# Adapterplatine.net
KiCad netlist of a schematic drawn in EAGLE
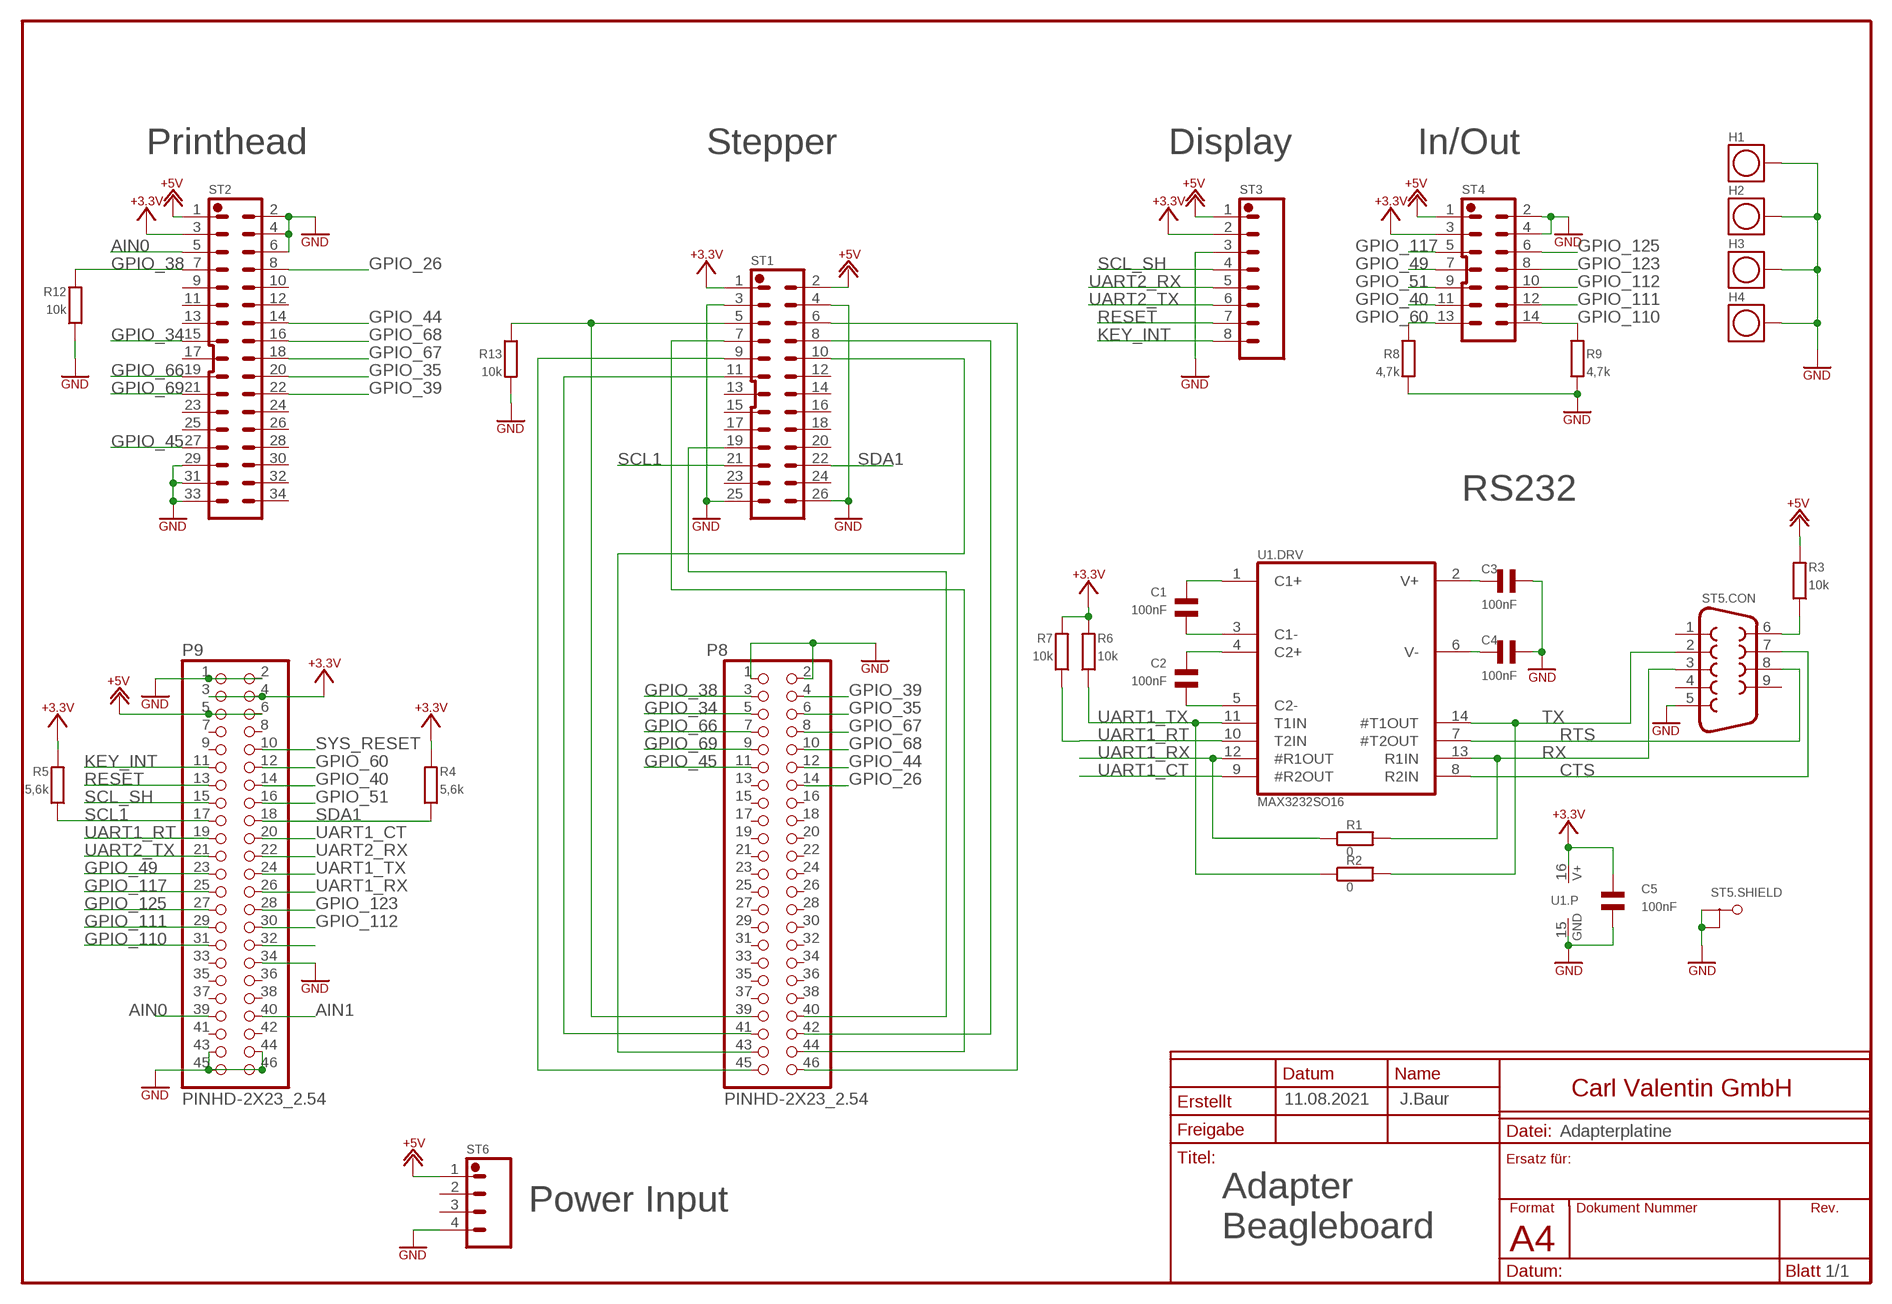
[diagram p0: schematic, sheet 1]

(export (version "E")
  (design (tool "Eeschema 10.0.6"))
  (components
    (comp (ref "C1")
      (value "100nF")
      (footprint "eagle-import:0603L")
      (libsource (lib "eagle-import") (part "C0603L"))
    )
    (comp (ref "C2")
      (value "100nF")
      (footprint "eagle-import:0603L")
      (libsource (lib "eagle-import") (part "C0603L"))
    )
    (comp (ref "C3")
      (value "100nF")
      (footprint "eagle-import:0603L")
      (libsource (lib "eagle-import") (part "C0603L"))
    )
    (comp (ref "C4")
      (value "100nF")
      (footprint "eagle-import:0603L")
      (libsource (lib "eagle-import") (part "C0603L"))
    )
    (comp (ref "C5")
      (value "100nF")
      (footprint "eagle-import:0603L")
      (libsource (lib "eagle-import") (part "C0603L"))
    )
    (comp (ref "H1")
      (value "HALTERUNG_SQUAREHALTERUNG_SQUARE_6.5_3.5")
      (footprint "eagle-import:HALTERUNG_SQUARE_6.5_3.5")
      (libsource (lib "eagle-import") (part "HALTERUNG_SQUAREHALTERUNG_SQUARE_6.5_3.5"))
    )
    (comp (ref "H2")
      (value "HALTERUNG_SQUAREHALTERUNG_SQUARE_6.5_3.5")
      (footprint "eagle-import:HALTERUNG_SQUARE_6.5_3.5")
      (libsource (lib "eagle-import") (part "HALTERUNG_SQUAREHALTERUNG_SQUARE_6.5_3.5"))
    )
    (comp (ref "H3")
      (value "HALTERUNG_SQUAREHALTERUNG_SQUARE_6.5_3.5")
      (footprint "eagle-import:HALTERUNG_SQUARE_6.5_3.5")
      (libsource (lib "eagle-import") (part "HALTERUNG_SQUAREHALTERUNG_SQUARE_6.5_3.5"))
    )
    (comp (ref "H4")
      (value "HALTERUNG_SQUAREHALTERUNG_SQUARE_6.5_3.5")
      (footprint "eagle-import:HALTERUNG_SQUARE_6.5_3.5")
      (libsource (lib "eagle-import") (part "HALTERUNG_SQUAREHALTERUNG_SQUARE_6.5_3.5"))
    )
    (comp (ref "P8")
      (value "PINHD-2X23_2.54")
      (footprint "eagle-import:2X23")
      (libsource (lib "eagle-import") (part "PINHD-2X23_2.54"))
    )
    (comp (ref "P9")
      (value "PINHD-2X23_2.54")
      (footprint "eagle-import:2X23")
      (libsource (lib "eagle-import") (part "PINHD-2X23_2.54"))
    )
    (comp (ref "R1")
      (value "0")
      (footprint "eagle-import:0603L")
      (libsource (lib "eagle-import") (part "R0603L"))
    )
    (comp (ref "R2")
      (value "0")
      (footprint "eagle-import:0603L")
      (libsource (lib "eagle-import") (part "R0603L"))
    )
    (comp (ref "R3")
      (value "10k")
      (footprint "eagle-import:0603L")
      (libsource (lib "eagle-import") (part "R0603L"))
    )
    (comp (ref "R4")
      (value "5,6k")
      (footprint "eagle-import:0603L")
      (libsource (lib "eagle-import") (part "R0603L"))
    )
    (comp (ref "R5")
      (value "5,6k")
      (footprint "eagle-import:0603L")
      (libsource (lib "eagle-import") (part "R0603L"))
    )
    (comp (ref "R6")
      (value "10k")
      (footprint "eagle-import:0603L")
      (libsource (lib "eagle-import") (part "R0603L"))
    )
    (comp (ref "R7")
      (value "10k")
      (footprint "eagle-import:0603L")
      (libsource (lib "eagle-import") (part "R0603L"))
    )
    (comp (ref "R8")
      (value "4,7k")
      (footprint "eagle-import:0603L")
      (libsource (lib "eagle-import") (part "R0603L"))
    )
    (comp (ref "R9")
      (value "4,7k")
      (footprint "eagle-import:0603L")
      (libsource (lib "eagle-import") (part "R0603L"))
    )
    (comp (ref "R12")
      (value "10k")
      (footprint "eagle-import:0603L")
      (libsource (lib "eagle-import") (part "R0603L"))
    )
    (comp (ref "R13")
      (value "10k")
      (footprint "eagle-import:0603L")
      (libsource (lib "eagle-import") (part "R0603L"))
    )
    (comp (ref "ST1")
      (value "STK-26-2RJST-PHD_26_TH")
      (footprint "eagle-import:JST-PHD_26_TH")
      (libsource (lib "eagle-import") (part "STK-26-2RJST-PHD_26_TH"))
    )
    (comp (ref "ST2")
      (value "STK-34-2R-MJST-PHD_34_TH-D1.0")
      (footprint "eagle-import:JST-PHD_34_TH-D1.0")
      (libsource (lib "eagle-import") (part "STK-34-2R-MJST-PHD_34_TH-D1.0"))
    )
    (comp (ref "ST3")
      (value "STK-08-1RJST-PH_8_TH")
      (footprint "eagle-import:JST-PH_8_TH")
      (libsource (lib "eagle-import") (part "STK-08-1RJST-PH_8_TH"))
    )
    (comp (ref "ST4")
      (value "STK-14-2RJST-PHD_14_TH")
      (footprint "eagle-import:JST-PHD_14_TH")
      (libsource (lib "eagle-import") (part "STK-14-2RJST-PHD_14_TH"))
    )
    (comp (ref "ST5")
      (value "STK-09-SUBD-FSTK-09-SUBD-F-WSI")
      (footprint "eagle-import:STK-09-SUBD-F-WSI")
      (libsource (lib "eagle-import") (part "STK-09-SUBD-FSTK-09-SUBD-F-WSI"))
    )
    (comp (ref "ST6")
      (value "STK-04-1RJST-VH_4_TH")
      (footprint "eagle-import:JST-VH_4_TH")
      (libsource (lib "eagle-import") (part "STK-04-1RJST-VH_4_TH"))
    )
    (comp (ref "U1")
      (value "MAX3232SO16")
      (footprint "eagle-import:SO16")
      (libsource (lib "eagle-import") (part "MAX3232SO16"))
    )
  )
  (nets
    (net (code "1") (name "+3.3V") (class "Default")
      (node (ref "C5") (pin "P$2") (pinfunction "2_P$2") (pintype "passive"))
      (node (ref "P9") (pin "3") (pinfunction "3_3") (pintype "passive"))
      (node (ref "P9") (pin "4") (pinfunction "4_4") (pintype "passive"))
      (node (ref "R4") (pin "P$2") (pinfunction "2_P$2") (pintype "passive"))
      (node (ref "R5") (pin "P$2") (pinfunction "2_P$2") (pintype "passive"))
      (node (ref "R6") (pin "P$2") (pinfunction "2_P$2") (pintype "passive"))
      (node (ref "R7") (pin "P$2") (pinfunction "2_P$2") (pintype "passive"))
      (node (ref "ST1") (pin "1") (pinfunction "1_1") (pintype "passive"))
      (node (ref "ST2") (pin "3") (pinfunction "3_3") (pintype "passive"))
      (node (ref "ST3") (pin "2") (pinfunction "2_2") (pintype "passive"))
      (node (ref "ST4") (pin "3") (pinfunction "3_3") (pintype "passive"))
      (node (ref "U1") (pin "16") (pinfunction "V+_16") (pintype "passive"))
    )
    (net (code "2") (name "+5V") (class "Default")
      (node (ref "P9") (pin "5") (pinfunction "5_5") (pintype "passive"))
      (node (ref "P9") (pin "6") (pinfunction "6_6") (pintype "passive"))
      (node (ref "R3") (pin "P$2") (pinfunction "2_P$2") (pintype "passive"))
      (node (ref "ST1") (pin "2") (pinfunction "2_2") (pintype "passive"))
      (node (ref "ST2") (pin "1") (pinfunction "1_1") (pintype "passive"))
      (node (ref "ST3") (pin "1") (pinfunction "1_1") (pintype "passive"))
      (node (ref "ST4") (pin "1") (pinfunction "1_1") (pintype "passive"))
      (node (ref "ST6") (pin "1") (pinfunction "1_1") (pintype "passive"))
    )
    (net (code "3") (name "/AIN0") (class "Default")
      (node (ref "P9") (pin "39") (pinfunction "39_39") (pintype "passive"))
      (node (ref "ST2") (pin "5") (pinfunction "5_5") (pintype "passive"))
    )
    (net (code "4") (name "/AIN1") (class "Default")
      (node (ref "P9") (pin "40") (pinfunction "40_40") (pintype "passive"))
    )
    (net (code "5") (name "/CTS") (class "Default")
      (node (ref "ST5") (pin "7") (pinfunction "7_7") (pintype "passive"))
      (node (ref "U1") (pin "8") (pinfunction "R2IN_8") (pintype "passive"))
    )
    (net (code "6") (name "/GPIO_26") (class "Default")
      (node (ref "P8") (pin "14") (pinfunction "14_14") (pintype "passive"))
      (node (ref "ST2") (pin "8") (pinfunction "8_8") (pintype "passive"))
    )
    (net (code "7") (name "/GPIO_34") (class "Default")
      (node (ref "P8") (pin "5") (pinfunction "5_5") (pintype "passive"))
      (node (ref "ST2") (pin "15") (pinfunction "15_15") (pintype "passive"))
    )
    (net (code "8") (name "/GPIO_35") (class "Default")
      (node (ref "P8") (pin "6") (pinfunction "6_6") (pintype "passive"))
      (node (ref "ST2") (pin "20") (pinfunction "20_20") (pintype "passive"))
    )
    (net (code "9") (name "/GPIO_38") (class "Default")
      (node (ref "P8") (pin "3") (pinfunction "3_3") (pintype "passive"))
      (node (ref "R12") (pin "P$2") (pinfunction "2_P$2") (pintype "passive"))
      (node (ref "ST2") (pin "7") (pinfunction "7_7") (pintype "passive"))
    )
    (net (code "10") (name "/GPIO_39") (class "Default")
      (node (ref "P8") (pin "4") (pinfunction "4_4") (pintype "passive"))
      (node (ref "ST2") (pin "22") (pinfunction "22_22") (pintype "passive"))
    )
    (net (code "11") (name "/GPIO_40") (class "Default")
      (node (ref "P9") (pin "14") (pinfunction "14_14") (pintype "passive"))
      (node (ref "ST4") (pin "11") (pinfunction "11_11") (pintype "passive"))
    )
    (net (code "12") (name "/GPIO_44") (class "Default")
      (node (ref "P8") (pin "12") (pinfunction "12_12") (pintype "passive"))
      (node (ref "ST2") (pin "14") (pinfunction "14_14") (pintype "passive"))
    )
    (net (code "13") (name "/GPIO_45") (class "Default")
      (node (ref "P8") (pin "11") (pinfunction "11_11") (pintype "passive"))
      (node (ref "ST2") (pin "27") (pinfunction "27_27") (pintype "passive"))
    )
    (net (code "14") (name "/GPIO_49") (class "Default")
      (node (ref "P9") (pin "23") (pinfunction "23_23") (pintype "passive"))
      (node (ref "ST4") (pin "7") (pinfunction "7_7") (pintype "passive"))
    )
    (net (code "15") (name "/GPIO_51") (class "Default")
      (node (ref "P9") (pin "16") (pinfunction "16_16") (pintype "passive"))
      (node (ref "ST4") (pin "9") (pinfunction "9_9") (pintype "passive"))
    )
    (net (code "16") (name "/GPIO_60") (class "Default")
      (node (ref "P9") (pin "12") (pinfunction "12_12") (pintype "passive"))
      (node (ref "R8") (pin "P$2") (pinfunction "2_P$2") (pintype "passive"))
      (node (ref "ST4") (pin "13") (pinfunction "13_13") (pintype "passive"))
    )
    (net (code "17") (name "/GPIO_66") (class "Default")
      (node (ref "P8") (pin "7") (pinfunction "7_7") (pintype "passive"))
      (node (ref "ST2") (pin "19") (pinfunction "19_19") (pintype "passive"))
    )
    (net (code "18") (name "/GPIO_67") (class "Default")
      (node (ref "P8") (pin "8") (pinfunction "8_8") (pintype "passive"))
      (node (ref "ST2") (pin "18") (pinfunction "18_18") (pintype "passive"))
    )
    (net (code "19") (name "/GPIO_68") (class "Default")
      (node (ref "P8") (pin "10") (pinfunction "10_10") (pintype "passive"))
      (node (ref "ST2") (pin "16") (pinfunction "16_16") (pintype "passive"))
    )
    (net (code "20") (name "/GPIO_69") (class "Default")
      (node (ref "P8") (pin "9") (pinfunction "9_9") (pintype "passive"))
      (node (ref "ST2") (pin "21") (pinfunction "21_21") (pintype "passive"))
    )
    (net (code "21") (name "/GPIO_110") (class "Default")
      (node (ref "P9") (pin "31") (pinfunction "31_31") (pintype "passive"))
      (node (ref "R9") (pin "P$2") (pinfunction "2_P$2") (pintype "passive"))
      (node (ref "ST4") (pin "14") (pinfunction "14_14") (pintype "passive"))
    )
    (net (code "22") (name "/GPIO_111") (class "Default")
      (node (ref "P9") (pin "29") (pinfunction "29_29") (pintype "passive"))
      (node (ref "ST4") (pin "12") (pinfunction "12_12") (pintype "passive"))
    )
    (net (code "23") (name "/GPIO_112") (class "Default")
      (node (ref "P9") (pin "30") (pinfunction "30_30") (pintype "passive"))
      (node (ref "ST4") (pin "10") (pinfunction "10_10") (pintype "passive"))
    )
    (net (code "24") (name "/GPIO_117") (class "Default")
      (node (ref "P9") (pin "25") (pinfunction "25_25") (pintype "passive"))
      (node (ref "ST4") (pin "5") (pinfunction "5_5") (pintype "passive"))
    )
    (net (code "25") (name "/GPIO_123") (class "Default")
      (node (ref "P9") (pin "28") (pinfunction "28_28") (pintype "passive"))
      (node (ref "ST4") (pin "8") (pinfunction "8_8") (pintype "passive"))
    )
    (net (code "26") (name "/GPIO_125") (class "Default")
      (node (ref "P9") (pin "27") (pinfunction "27_27") (pintype "passive"))
      (node (ref "ST4") (pin "6") (pinfunction "6_6") (pintype "passive"))
    )
    (net (code "27") (name "/KEY_INT") (class "Default")
      (node (ref "P9") (pin "11") (pinfunction "11_11") (pintype "passive"))
      (node (ref "ST3") (pin "8") (pinfunction "8_8") (pintype "passive"))
    )
    (net (code "28") (name "/RESET") (class "Default")
      (node (ref "P9") (pin "13") (pinfunction "13_13") (pintype "passive"))
      (node (ref "ST3") (pin "7") (pinfunction "7_7") (pintype "passive"))
    )
    (net (code "29") (name "/RTS") (class "Default")
      (node (ref "ST5") (pin "8") (pinfunction "8_8") (pintype "passive"))
      (node (ref "U1") (pin "7") (pinfunction "#T2OUT_7") (pintype "passive"))
    )
    (net (code "30") (name "/RX") (class "Default")
      (node (ref "R1") (pin "P$2") (pinfunction "2_P$2") (pintype "passive"))
      (node (ref "ST5") (pin "3") (pinfunction "3_3") (pintype "passive"))
      (node (ref "U1") (pin "13") (pinfunction "R1IN_13") (pintype "passive"))
    )
    (net (code "31") (name "/SCL1") (class "Default")
      (node (ref "P9") (pin "17") (pinfunction "17_17") (pintype "passive"))
      (node (ref "R5") (pin "P$1") (pinfunction "1_P$1") (pintype "passive"))
      (node (ref "ST1") (pin "21") (pinfunction "21_21") (pintype "passive"))
    )
    (net (code "32") (name "/SCL_SH") (class "Default")
      (node (ref "P9") (pin "15") (pinfunction "15_15") (pintype "passive"))
      (node (ref "ST3") (pin "4") (pinfunction "4_4") (pintype "passive"))
    )
    (net (code "33") (name "/SDA1") (class "Default")
      (node (ref "P9") (pin "18") (pinfunction "18_18") (pintype "passive"))
      (node (ref "R4") (pin "P$1") (pinfunction "1_P$1") (pintype "passive"))
      (node (ref "ST1") (pin "22") (pinfunction "22_22") (pintype "passive"))
    )
    (net (code "34") (name "/SYS_RESET") (class "Default")
      (node (ref "P9") (pin "10") (pinfunction "10_10") (pintype "passive"))
    )
    (net (code "35") (name "/TX") (class "Default")
      (node (ref "R2") (pin "P$2") (pinfunction "2_P$2") (pintype "passive"))
      (node (ref "ST5") (pin "2") (pinfunction "2_2") (pintype "passive"))
      (node (ref "U1") (pin "14") (pinfunction "#T1OUT_14") (pintype "passive"))
    )
    (net (code "36") (name "/UART1_CT") (class "Default")
      (node (ref "P9") (pin "20") (pinfunction "20_20") (pintype "passive"))
      (node (ref "U1") (pin "9") (pinfunction "#R2OUT_9") (pintype "passive"))
    )
    (net (code "37") (name "/UART1_RT") (class "Default")
      (node (ref "P9") (pin "19") (pinfunction "19_19") (pintype "passive"))
      (node (ref "R7") (pin "P$1") (pinfunction "1_P$1") (pintype "passive"))
      (node (ref "U1") (pin "10") (pinfunction "T2IN_10") (pintype "passive"))
    )
    (net (code "38") (name "/UART1_RX") (class "Default")
      (node (ref "P9") (pin "26") (pinfunction "26_26") (pintype "passive"))
      (node (ref "R1") (pin "P$1") (pinfunction "1_P$1") (pintype "passive"))
      (node (ref "U1") (pin "12") (pinfunction "#R1OUT_12") (pintype "passive"))
    )
    (net (code "39") (name "/UART1_TX") (class "Default")
      (node (ref "P9") (pin "24") (pinfunction "24_24") (pintype "passive"))
      (node (ref "R2") (pin "P$1") (pinfunction "1_P$1") (pintype "passive"))
      (node (ref "R6") (pin "P$1") (pinfunction "1_P$1") (pintype "passive"))
      (node (ref "U1") (pin "11") (pinfunction "T1IN_11") (pintype "passive"))
    )
    (net (code "40") (name "/UART2_RX") (class "Default")
      (node (ref "P9") (pin "22") (pinfunction "22_22") (pintype "passive"))
      (node (ref "ST3") (pin "5") (pinfunction "5_5") (pintype "passive"))
    )
    (net (code "41") (name "/UART2_TX") (class "Default")
      (node (ref "P9") (pin "21") (pinfunction "21_21") (pintype "passive"))
      (node (ref "ST3") (pin "6") (pinfunction "6_6") (pintype "passive"))
    )
    (net (code "42") (name "GND") (class "Default")
      (node (ref "C3") (pin "P$1") (pinfunction "1_P$1") (pintype "passive"))
      (node (ref "C4") (pin "P$2") (pinfunction "2_P$2") (pintype "passive"))
      (node (ref "C5") (pin "P$1") (pinfunction "1_P$1") (pintype "passive"))
      (node (ref "H1") (pin "P$1") (pinfunction "P$1_P$1") (pintype "passive"))
      (node (ref "H2") (pin "P$1") (pinfunction "P$1_P$1") (pintype "passive"))
      (node (ref "H3") (pin "P$1") (pinfunction "P$1_P$1") (pintype "passive"))
      (node (ref "H4") (pin "P$1") (pinfunction "P$1_P$1") (pintype "passive"))
      (node (ref "P8") (pin "1") (pinfunction "1_1") (pintype "passive"))
      (node (ref "P8") (pin "2") (pinfunction "2_2") (pintype "passive"))
      (node (ref "P9") (pin "1") (pinfunction "1_1") (pintype "passive"))
      (node (ref "P9") (pin "2") (pinfunction "2_2") (pintype "passive"))
      (node (ref "P9") (pin "34") (pinfunction "34_34") (pintype "passive"))
      (node (ref "P9") (pin "43") (pinfunction "43_43") (pintype "passive"))
      (node (ref "P9") (pin "44") (pinfunction "44_44") (pintype "passive"))
      (node (ref "P9") (pin "45") (pinfunction "45_45") (pintype "passive"))
      (node (ref "P9") (pin "46") (pinfunction "46_46") (pintype "passive"))
      (node (ref "R12") (pin "P$1") (pinfunction "1_P$1") (pintype "passive"))
      (node (ref "R13") (pin "P$2") (pinfunction "2_P$2") (pintype "passive"))
      (node (ref "R8") (pin "P$1") (pinfunction "1_P$1") (pintype "passive"))
      (node (ref "R9") (pin "P$1") (pinfunction "1_P$1") (pintype "passive"))
      (node (ref "ST1") (pin "25") (pinfunction "25_25") (pintype "passive"))
      (node (ref "ST1") (pin "26") (pinfunction "26_26") (pintype "passive"))
      (node (ref "ST1") (pin "3") (pinfunction "3_3") (pintype "passive"))
      (node (ref "ST1") (pin "4") (pinfunction "4_4") (pintype "passive"))
      (node (ref "ST2") (pin "2") (pinfunction "2_2") (pintype "passive"))
      (node (ref "ST2") (pin "29") (pinfunction "29_29") (pintype "passive"))
      (node (ref "ST2") (pin "31") (pinfunction "31_31") (pintype "passive"))
      (node (ref "ST2") (pin "33") (pinfunction "33_33") (pintype "passive"))
      (node (ref "ST2") (pin "4") (pinfunction "4_4") (pintype "passive"))
      (node (ref "ST2") (pin "6") (pinfunction "6_6") (pintype "passive"))
      (node (ref "ST3") (pin "3") (pinfunction "3_3") (pintype "passive"))
      (node (ref "ST4") (pin "2") (pinfunction "2_2") (pintype "passive"))
      (node (ref "ST4") (pin "4") (pinfunction "4_4") (pintype "passive"))
      (node (ref "ST5") (pin "5") (pinfunction "5_5") (pintype "passive"))
      (node (ref "ST5") (pin "G1") (pinfunction "S1_G1") (pintype "passive"))
      (node (ref "ST5") (pin "G2") (pinfunction "S2_G2") (pintype "passive"))
      (node (ref "ST6") (pin "4") (pinfunction "4_4") (pintype "passive"))
      (node (ref "U1") (pin "15") (pinfunction "GND_15") (pintype "passive"))
    )
    (net (code "43") (name "Net-(C1-1)") (class "Default")
      (node (ref "C1") (pin "P$1") (pinfunction "1_P$1") (pintype "passive"))
      (node (ref "U1") (pin "3") (pinfunction "C1-_3") (pintype "passive"))
    )
    (net (code "44") (name "Net-(C1-2)") (class "Default")
      (node (ref "C1") (pin "P$2") (pinfunction "2_P$2") (pintype "passive"))
      (node (ref "U1") (pin "1") (pinfunction "C1+_1") (pintype "passive"))
    )
    (net (code "45") (name "Net-(C2-1)") (class "Default")
      (node (ref "C2") (pin "P$1") (pinfunction "1_P$1") (pintype "passive"))
      (node (ref "U1") (pin "5") (pinfunction "C2-_5") (pintype "passive"))
    )
    (net (code "46") (name "Net-(C2-2)") (class "Default")
      (node (ref "C2") (pin "P$2") (pinfunction "2_P$2") (pintype "passive"))
      (node (ref "U1") (pin "4") (pinfunction "C2+_4") (pintype "passive"))
    )
    (net (code "47") (name "Net-(C3-2)") (class "Default")
      (node (ref "C3") (pin "P$2") (pinfunction "2_P$2") (pintype "passive"))
      (node (ref "U1") (pin "2") (pinfunction "V+_2") (pintype "passive"))
    )
    (net (code "48") (name "Net-(C4-1)") (class "Default")
      (node (ref "C4") (pin "P$1") (pinfunction "1_P$1") (pintype "passive"))
      (node (ref "U1") (pin "6") (pinfunction "V-_6") (pintype "passive"))
    )
    (net (code "49") (name "Net-(P8-Pad40)") (class "Default")
      (node (ref "P8") (pin "40") (pinfunction "40_40") (pintype "passive"))
      (node (ref "ST1") (pin "19") (pinfunction "19_19") (pintype "passive"))
    )
    (net (code "50") (name "Net-(P8-Pad41)") (class "Default")
      (node (ref "P8") (pin "41") (pinfunction "41_41") (pintype "passive"))
      (node (ref "ST1") (pin "11") (pinfunction "11_11") (pintype "passive"))
    )
    (net (code "51") (name "Net-(P8-Pad42)") (class "Default")
      (node (ref "P8") (pin "42") (pinfunction "42_42") (pintype "passive"))
      (node (ref "ST1") (pin "8") (pinfunction "8_8") (pintype "passive"))
    )
    (net (code "52") (name "Net-(P8-Pad43)") (class "Default")
      (node (ref "P8") (pin "43") (pinfunction "43_43") (pintype "passive"))
      (node (ref "ST1") (pin "10") (pinfunction "10_10") (pintype "passive"))
    )
    (net (code "53") (name "Net-(P8-Pad44)") (class "Default")
      (node (ref "P8") (pin "44") (pinfunction "44_44") (pintype "passive"))
      (node (ref "ST1") (pin "7") (pinfunction "7_7") (pintype "passive"))
    )
    (net (code "54") (name "Net-(P8-Pad45)") (class "Default")
      (node (ref "P8") (pin "45") (pinfunction "45_45") (pintype "passive"))
      (node (ref "ST1") (pin "9") (pinfunction "9_9") (pintype "passive"))
    )
    (net (code "55") (name "Net-(P8-Pad46)") (class "Default")
      (node (ref "P8") (pin "46") (pinfunction "46_46") (pintype "passive"))
      (node (ref "ST1") (pin "6") (pinfunction "6_6") (pintype "passive"))
    )
    (net (code "56") (name "Net-(R3-1)") (class "Default")
      (node (ref "R3") (pin "P$1") (pinfunction "1_P$1") (pintype "passive"))
      (node (ref "ST5") (pin "6") (pinfunction "6_6") (pintype "passive"))
    )
    (net (code "57") (name "Net-(R13-1)") (class "Default")
      (node (ref "P8") (pin "39") (pinfunction "39_39") (pintype "passive"))
      (node (ref "R13") (pin "P$1") (pinfunction "1_P$1") (pintype "passive"))
      (node (ref "ST1") (pin "5") (pinfunction "5_5") (pintype "passive"))
    )
    (net (code "58") (name "unconnected-(P8-Pad13)") (class "Default")
      (node (ref "P8") (pin "13") (pinfunction "13_13") (pintype "passive"))
    )
    (net (code "59") (name "unconnected-(P8-Pad15)") (class "Default")
      (node (ref "P8") (pin "15") (pinfunction "15_15") (pintype "passive"))
    )
    (net (code "60") (name "unconnected-(P8-Pad16)") (class "Default")
      (node (ref "P8") (pin "16") (pinfunction "16_16") (pintype "passive"))
    )
    (net (code "61") (name "unconnected-(P8-Pad17)") (class "Default")
      (node (ref "P8") (pin "17") (pinfunction "17_17") (pintype "passive"))
    )
    (net (code "62") (name "unconnected-(P8-Pad18)") (class "Default")
      (node (ref "P8") (pin "18") (pinfunction "18_18") (pintype "passive"))
    )
    (net (code "63") (name "unconnected-(P8-Pad19)") (class "Default")
      (node (ref "P8") (pin "19") (pinfunction "19_19") (pintype "passive"))
    )
    (net (code "64") (name "unconnected-(P8-Pad20)") (class "Default")
      (node (ref "P8") (pin "20") (pinfunction "20_20") (pintype "passive"))
    )
    (net (code "65") (name "unconnected-(P8-Pad21)") (class "Default")
      (node (ref "P8") (pin "21") (pinfunction "21_21") (pintype "passive"))
    )
    (net (code "66") (name "unconnected-(P8-Pad22)") (class "Default")
      (node (ref "P8") (pin "22") (pinfunction "22_22") (pintype "passive"))
    )
    (net (code "67") (name "unconnected-(P8-Pad23)") (class "Default")
      (node (ref "P8") (pin "23") (pinfunction "23_23") (pintype "passive"))
    )
    (net (code "68") (name "unconnected-(P8-Pad24)") (class "Default")
      (node (ref "P8") (pin "24") (pinfunction "24_24") (pintype "passive"))
    )
    (net (code "69") (name "unconnected-(P8-Pad25)") (class "Default")
      (node (ref "P8") (pin "25") (pinfunction "25_25") (pintype "passive"))
    )
    (net (code "70") (name "unconnected-(P8-Pad26)") (class "Default")
      (node (ref "P8") (pin "26") (pinfunction "26_26") (pintype "passive"))
    )
    (net (code "71") (name "unconnected-(P8-Pad27)") (class "Default")
      (node (ref "P8") (pin "27") (pinfunction "27_27") (pintype "passive"))
    )
    (net (code "72") (name "unconnected-(P8-Pad28)") (class "Default")
      (node (ref "P8") (pin "28") (pinfunction "28_28") (pintype "passive"))
    )
    (net (code "73") (name "unconnected-(P8-Pad29)") (class "Default")
      (node (ref "P8") (pin "29") (pinfunction "29_29") (pintype "passive"))
    )
    (net (code "74") (name "unconnected-(P8-Pad30)") (class "Default")
      (node (ref "P8") (pin "30") (pinfunction "30_30") (pintype "passive"))
    )
    (net (code "75") (name "unconnected-(P8-Pad31)") (class "Default")
      (node (ref "P8") (pin "31") (pinfunction "31_31") (pintype "passive"))
    )
    (net (code "76") (name "unconnected-(P8-Pad32)") (class "Default")
      (node (ref "P8") (pin "32") (pinfunction "32_32") (pintype "passive"))
    )
    (net (code "77") (name "unconnected-(P8-Pad33)") (class "Default")
      (node (ref "P8") (pin "33") (pinfunction "33_33") (pintype "passive"))
    )
    (net (code "78") (name "unconnected-(P8-Pad34)") (class "Default")
      (node (ref "P8") (pin "34") (pinfunction "34_34") (pintype "passive"))
    )
    (net (code "79") (name "unconnected-(P8-Pad35)") (class "Default")
      (node (ref "P8") (pin "35") (pinfunction "35_35") (pintype "passive"))
    )
    (net (code "80") (name "unconnected-(P8-Pad36)") (class "Default")
      (node (ref "P8") (pin "36") (pinfunction "36_36") (pintype "passive"))
    )
    (net (code "81") (name "unconnected-(P8-Pad37)") (class "Default")
      (node (ref "P8") (pin "37") (pinfunction "37_37") (pintype "passive"))
    )
    (net (code "82") (name "unconnected-(P8-Pad38)") (class "Default")
      (node (ref "P8") (pin "38") (pinfunction "38_38") (pintype "passive"))
    )
    (net (code "83") (name "unconnected-(P9-Pad7)") (class "Default")
      (node (ref "P9") (pin "7") (pinfunction "7_7") (pintype "passive"))
    )
    (net (code "84") (name "unconnected-(P9-Pad8)") (class "Default")
      (node (ref "P9") (pin "8") (pinfunction "8_8") (pintype "passive"))
    )
    (net (code "85") (name "unconnected-(P9-Pad9)") (class "Default")
      (node (ref "P9") (pin "9") (pinfunction "9_9") (pintype "passive"))
    )
    (net (code "86") (name "unconnected-(P9-Pad32)") (class "Default")
      (node (ref "P9") (pin "32") (pinfunction "32_32") (pintype "passive"))
    )
    (net (code "87") (name "unconnected-(P9-Pad33)") (class "Default")
      (node (ref "P9") (pin "33") (pinfunction "33_33") (pintype "passive"))
    )
    (net (code "88") (name "unconnected-(P9-Pad35)") (class "Default")
      (node (ref "P9") (pin "35") (pinfunction "35_35") (pintype "passive"))
    )
    (net (code "89") (name "unconnected-(P9-Pad36)") (class "Default")
      (node (ref "P9") (pin "36") (pinfunction "36_36") (pintype "passive"))
    )
    (net (code "90") (name "unconnected-(P9-Pad37)") (class "Default")
      (node (ref "P9") (pin "37") (pinfunction "37_37") (pintype "passive"))
    )
    (net (code "91") (name "unconnected-(P9-Pad38)") (class "Default")
      (node (ref "P9") (pin "38") (pinfunction "38_38") (pintype "passive"))
    )
    (net (code "92") (name "unconnected-(P9-Pad41)") (class "Default")
      (node (ref "P9") (pin "41") (pinfunction "41_41") (pintype "passive"))
    )
    (net (code "93") (name "unconnected-(P9-Pad42)") (class "Default")
      (node (ref "P9") (pin "42") (pinfunction "42_42") (pintype "passive"))
    )
    (net (code "94") (name "unconnected-(ST1-Pad12)") (class "Default")
      (node (ref "ST1") (pin "12") (pinfunction "12_12") (pintype "passive"))
    )
    (net (code "95") (name "unconnected-(ST1-Pad13)") (class "Default")
      (node (ref "ST1") (pin "13") (pinfunction "13_13") (pintype "passive"))
    )
    (net (code "96") (name "unconnected-(ST1-Pad14)") (class "Default")
      (node (ref "ST1") (pin "14") (pinfunction "14_14") (pintype "passive"))
    )
    (net (code "97") (name "unconnected-(ST1-Pad15)") (class "Default")
      (node (ref "ST1") (pin "15") (pinfunction "15_15") (pintype "passive"))
    )
    (net (code "98") (name "unconnected-(ST1-Pad16)") (class "Default")
      (node (ref "ST1") (pin "16") (pinfunction "16_16") (pintype "passive"))
    )
    (net (code "99") (name "unconnected-(ST1-Pad17)") (class "Default")
      (node (ref "ST1") (pin "17") (pinfunction "17_17") (pintype "passive"))
    )
    (net (code "100") (name "unconnected-(ST1-Pad18)") (class "Default")
      (node (ref "ST1") (pin "18") (pinfunction "18_18") (pintype "passive"))
    )
    (net (code "101") (name "unconnected-(ST1-Pad20)") (class "Default")
      (node (ref "ST1") (pin "20") (pinfunction "20_20") (pintype "passive"))
    )
    (net (code "102") (name "unconnected-(ST1-Pad23)") (class "Default")
      (node (ref "ST1") (pin "23") (pinfunction "23_23") (pintype "passive"))
    )
    (net (code "103") (name "unconnected-(ST1-Pad24)") (class "Default")
      (node (ref "ST1") (pin "24") (pinfunction "24_24") (pintype "passive"))
    )
    (net (code "104") (name "unconnected-(ST2-Pad9)") (class "Default")
      (node (ref "ST2") (pin "9") (pinfunction "9_9") (pintype "passive"))
    )
    (net (code "105") (name "unconnected-(ST2-Pad10)") (class "Default")
      (node (ref "ST2") (pin "10") (pinfunction "10_10") (pintype "passive"))
    )
    (net (code "106") (name "unconnected-(ST2-Pad11)") (class "Default")
      (node (ref "ST2") (pin "11") (pinfunction "11_11") (pintype "passive"))
    )
    (net (code "107") (name "unconnected-(ST2-Pad12)") (class "Default")
      (node (ref "ST2") (pin "12") (pinfunction "12_12") (pintype "passive"))
    )
    (net (code "108") (name "unconnected-(ST2-Pad13)") (class "Default")
      (node (ref "ST2") (pin "13") (pinfunction "13_13") (pintype "passive"))
    )
    (net (code "109") (name "unconnected-(ST2-Pad17)") (class "Default")
      (node (ref "ST2") (pin "17") (pinfunction "17_17") (pintype "passive"))
    )
    (net (code "110") (name "unconnected-(ST2-Pad23)") (class "Default")
      (node (ref "ST2") (pin "23") (pinfunction "23_23") (pintype "passive"))
    )
    (net (code "111") (name "unconnected-(ST2-Pad24)") (class "Default")
      (node (ref "ST2") (pin "24") (pinfunction "24_24") (pintype "passive"))
    )
    (net (code "112") (name "unconnected-(ST2-Pad25)") (class "Default")
      (node (ref "ST2") (pin "25") (pinfunction "25_25") (pintype "passive"))
    )
    (net (code "113") (name "unconnected-(ST2-Pad26)") (class "Default")
      (node (ref "ST2") (pin "26") (pinfunction "26_26") (pintype "passive"))
    )
    (net (code "114") (name "unconnected-(ST2-Pad28)") (class "Default")
      (node (ref "ST2") (pin "28") (pinfunction "28_28") (pintype "passive"))
    )
    (net (code "115") (name "unconnected-(ST2-Pad30)") (class "Default")
      (node (ref "ST2") (pin "30") (pinfunction "30_30") (pintype "passive"))
    )
    (net (code "116") (name "unconnected-(ST2-Pad32)") (class "Default")
      (node (ref "ST2") (pin "32") (pinfunction "32_32") (pintype "passive"))
    )
    (net (code "117") (name "unconnected-(ST2-Pad34)") (class "Default")
      (node (ref "ST2") (pin "34") (pinfunction "34_34") (pintype "passive"))
    )
    (net (code "118") (name "unconnected-(ST5-Pad1)") (class "Default")
      (node (ref "ST5") (pin "1") (pinfunction "1_1") (pintype "passive"))
    )
    (net (code "119") (name "unconnected-(ST5-Pad4)") (class "Default")
      (node (ref "ST5") (pin "4") (pinfunction "4_4") (pintype "passive"))
    )
    (net (code "120") (name "unconnected-(ST5-Pad9)") (class "Default")
      (node (ref "ST5") (pin "9") (pinfunction "9_9") (pintype "passive"))
    )
    (net (code "121") (name "unconnected-(ST6-Pad2)") (class "Default")
      (node (ref "ST6") (pin "2") (pinfunction "2_2") (pintype "passive"))
    )
    (net (code "122") (name "unconnected-(ST6-Pad3)") (class "Default")
      (node (ref "ST6") (pin "3") (pinfunction "3_3") (pintype "passive"))
    )
  )
)
